# Synch_Demod.net
KiCad netlist of a schematic drawn in Altium Designer
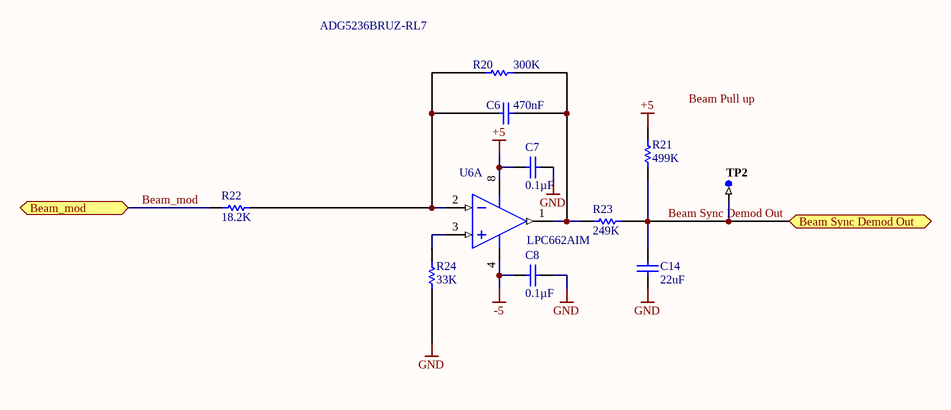
[diagram p0: Synch_Demod.SchDoc]

(export (version "E")
  (design (tool "Eeschema 10.0.6"))
  (components
    (comp (ref "C6")
      (value "470nF")
      (footprint "CAPC0805(2012)75_L")
      (description "CAP CER 0.47UF 25V X7R 0805")
      (fields
        (field (name "MANUFACTURER") "Murata Electronics North America")
        (field (name "MANUFACTURER PART NUMBER") "GRM219R71E474KA88D")
      )
      (libsource (lib "Altium Content Vault") (part "CMP-1036-02117-1"))
    )
    (comp (ref "C7")
      (value "CAP CER 0.1UF 25V X7R 0805")
      (footprint "CAPC0805(2012)145_N")
      (fields
        (field (name "MANUFACTURER") "Murata Electronics North America")
        (field (name "MANUFACTURER PART NUMBER") "GRM21BR71E104KA01L")
        (field (name "CAPACITANCE") "0.1µF")
        (field (name "TOLERANCE") "±10%")
      )
      (libsource (lib "Altium Content Vault") (part "CMP-1036-04795-1"))
    )
    (comp (ref "C8")
      (value "CAP CER 0.1UF 25V X7R 0805")
      (footprint "CAPC0805(2012)145_N")
      (fields
        (field (name "MANUFACTURER") "Murata Electronics North America")
        (field (name "MANUFACTURER PART NUMBER") "GRM21BR71E104KA01L")
        (field (name "CAPACITANCE") "0.1µF")
        (field (name "TOLERANCE") "±10%")
      )
      (libsource (lib "Altium Content Vault") (part "CMP-1036-04795-1"))
    )
    (comp (ref "C14")
      (value "22uF")
      (footprint "CAPC0805(2012)75_L")
      (description "CAP CER 22UF 25V X5R 0805")
      (fields
        (field (name "MANUFACTURER") "Murata Electronics North America")
        (field (name "MANUFACTURER PART NUMBER") "GRM21BR61E226ME44L")
      )
      (libsource (lib "Altium Content Vault") (part "CMP-1036-02117-1"))
    )
    (comp (ref "R20")
      (value "300K")
      (footprint "RESC0805(2012)_L")
      (description "RES SMD 300K OHM 1% 1/8W 0805")
      (fields
        (field (name "MANUFACTURER") "Vishay Dale")
        (field (name "MANUFACTURER PART NUMBER") "CRCW0805300KFKEAHP")
      )
      (libsource (lib "Altium Content Vault") (part "CMP-1013-00215-1"))
    )
    (comp (ref "R21")
      (value "499K")
      (footprint "RESC0805(2012)_L")
      (description "RES SMD 499K OHM 0.1% 1/8W 0805")
      (fields
        (field (name "MANUFACTURER") "Panasonic Electronic Components")
        (field (name "MANUFACTURER PART NUMBER") "ERA-6AEB4993V")
      )
      (libsource (lib "Altium Content Vault") (part "CMP-1013-00215-1"))
    )
    (comp (ref "R22")
      (value "18.2K")
      (footprint "RESC0805(2012)_L")
      (description "RES SMD 18.2K OHM 1% 1/8W 0805")
      (fields
        (field (name "MANUFACTURER") "Panasonic Electronic Components")
        (field (name "MANUFACTURER PART NUMBER") "ERJ-6ENF1822V")
      )
      (libsource (lib "Altium Content Vault") (part "CMP-1013-00215-1"))
    )
    (comp (ref "R23")
      (value "249K")
      (footprint "RESC0805(2012)_L")
      (description "RES SMD 249K OHM 0.1% 1/8W 0805")
      (fields
        (field (name "MANUFACTURER") "Panasonic Electronic Components")
        (field (name "MANUFACTURER PART NUMBER") "ERA-6AEB2493V")
      )
      (libsource (lib "Altium Content Vault") (part "CMP-1013-00215-1"))
    )
    (comp (ref "R24")
      (value "33K")
      (footprint "RESC0805(2012)_L")
      (description "RES SMD 33K OHM 1% 1/2W 0805")
      (fields
        (field (name "MANUFACTURER") "Vishay Dale")
        (field (name "MANUFACTURER PART NUMBER") "CRCW080533K0FKEAHP")
      )
      (libsource (lib "Altium Content Vault") (part "CMP-1013-00215-1"))
    )
    (comp (ref "TP2")
      (value "TP-SM-C-100")
      (footprint "TP-SM-C-100")
      (description "Test Point, Surface Mount, Circular, Pad Diameter 1 mm")
      (fields (field (name "MANUFACTURER") "No Vendor"))
      (libsource (lib "Altium Content Vault") (part "CMP-0484-00002-2"))
    )
    (comp (ref "U6")
      (value "LPC662AIM")
      (footprint "D0008A_M")
      (description "Low Power CMOS Dual Operational Amplifier, 8-pin Narrow SOIC")
      (fields
        (field (name "MANUFACTURER") "Texas Instruments")
        (field (name "MANUFACTURER PART NUMBER") "LPC662AIM/NOPB")
      )
      (libsource (lib "Altium Content Vault") (part "CMP-0055-00867-3"))
    )
  )
  (nets
    (net (code "1") (name "+5") (class "Default")
      (node (ref "C7") (pin "1") (pinfunction "1_1") (pintype "passive"))
      (node (ref "R21") (pin "2") (pinfunction "2_2") (pintype "passive"))
      (node (ref "U6") (pin "8") (pinfunction "V+_8") (pintype "power_in"))
    )
    (net (code "2") (name "-5") (class "Default")
      (node (ref "C8") (pin "1") (pinfunction "1_1") (pintype "passive"))
      (node (ref "U6") (pin "4") (pinfunction "V-_4") (pintype "power_in"))
    )
    (net (code "4") (name "/Beam Sync Demod Out") (class "Default")
      (node (ref "C14") (pin "2") (pinfunction "2_2") (pintype "passive"))
      (node (ref "R21") (pin "1") (pinfunction "1_1") (pintype "passive"))
      (node (ref "R23") (pin "1") (pinfunction "1_1") (pintype "passive"))
      (node (ref "TP2") (pin "1") (pinfunction "1_1") (pintype "input"))
    )
    (net (code "5") (name "/Beam_mod") (class "Default")
      (node (ref "R22") (pin "2") (pinfunction "2_2") (pintype "passive"))
    )
    (net (code "6") (name "GND") (class "Default")
      (node (ref "C14") (pin "1") (pinfunction "1_1") (pintype "passive"))
      (node (ref "C7") (pin "2") (pinfunction "2_2") (pintype "passive"))
      (node (ref "C8") (pin "2") (pinfunction "2_2") (pintype "passive"))
      (node (ref "R24") (pin "1") (pinfunction "1_1") (pintype "passive"))
    )
    (net (code "7") (name "Net-(U6A-INA+)") (class "Default")
      (node (ref "R24") (pin "2") (pinfunction "2_2") (pintype "passive"))
      (node (ref "U6") (pin "3") (pinfunction "INA+_3") (pintype "input"))
    )
    (net (code "8") (name "Net-(U6A-INA-)") (class "Default")
      (node (ref "C6") (pin "1") (pinfunction "1_1") (pintype "passive"))
      (node (ref "R20") (pin "2") (pinfunction "2_2") (pintype "passive"))
      (node (ref "R22") (pin "1") (pinfunction "1_1") (pintype "passive"))
      (node (ref "U6") (pin "2") (pinfunction "INA-_2") (pintype "input"))
    )
    (net (code "9") (name "Net-(U6A-OUTA)") (class "Default")
      (node (ref "C6") (pin "2") (pinfunction "2_2") (pintype "passive"))
      (node (ref "R20") (pin "1") (pinfunction "1_1") (pintype "passive"))
      (node (ref "R23") (pin "2") (pinfunction "2_2") (pintype "passive"))
      (node (ref "U6") (pin "1") (pinfunction "OUTA_1") (pintype "output"))
    )
  )
)
